# FinalSchematic1_2.net
KiCad netlist of a schematic drawn in EAGLE
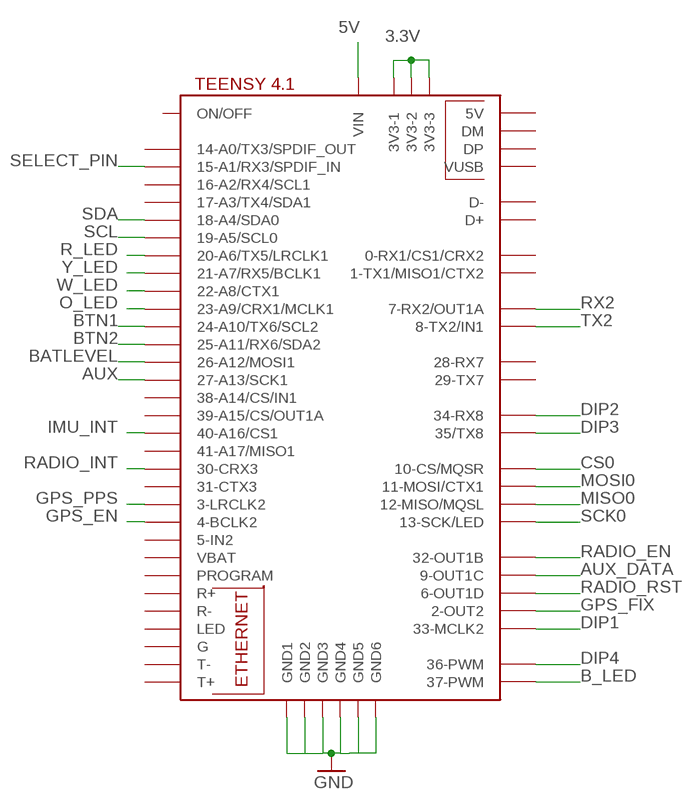
[diagram p0: schematic, sheet 1]
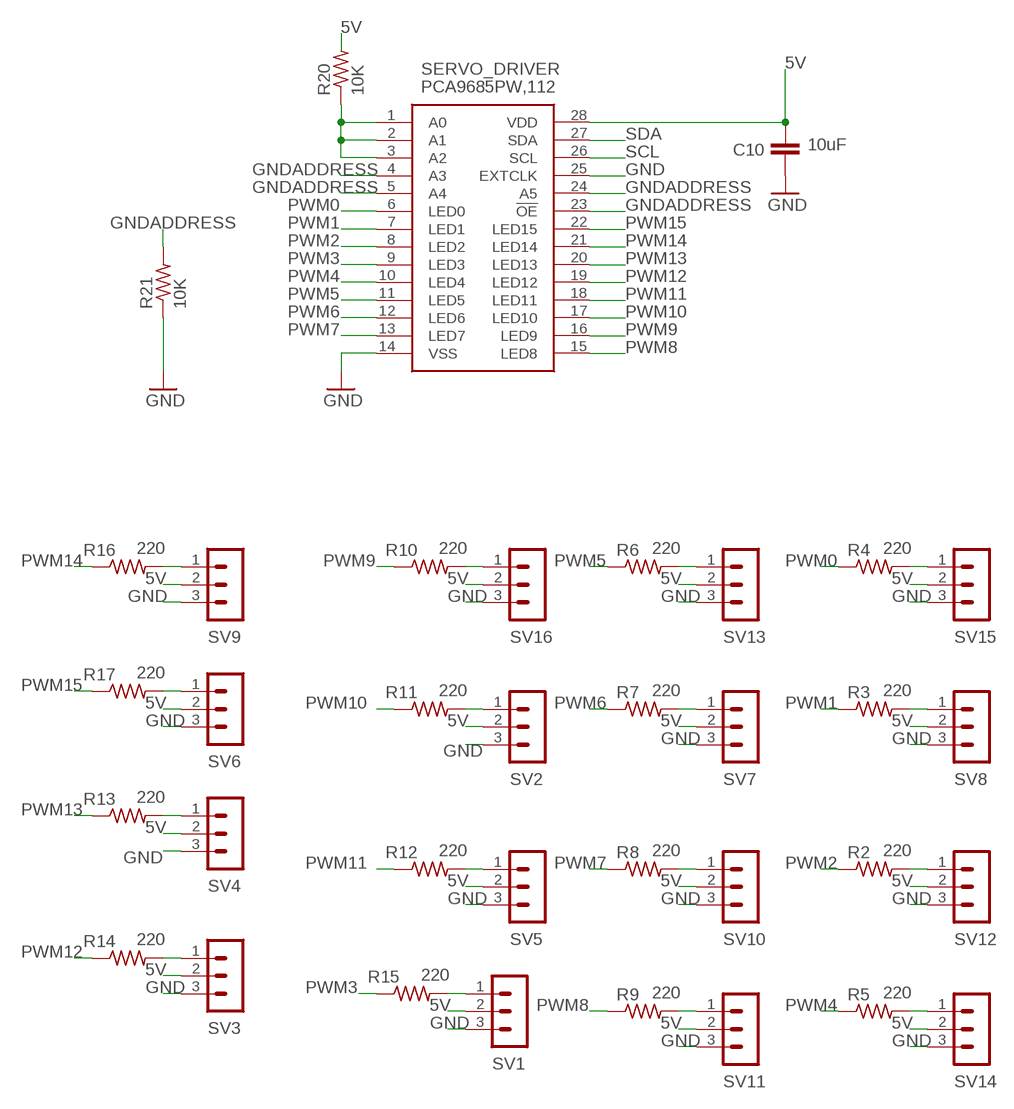
[diagram p1: schematic, sheet 2]
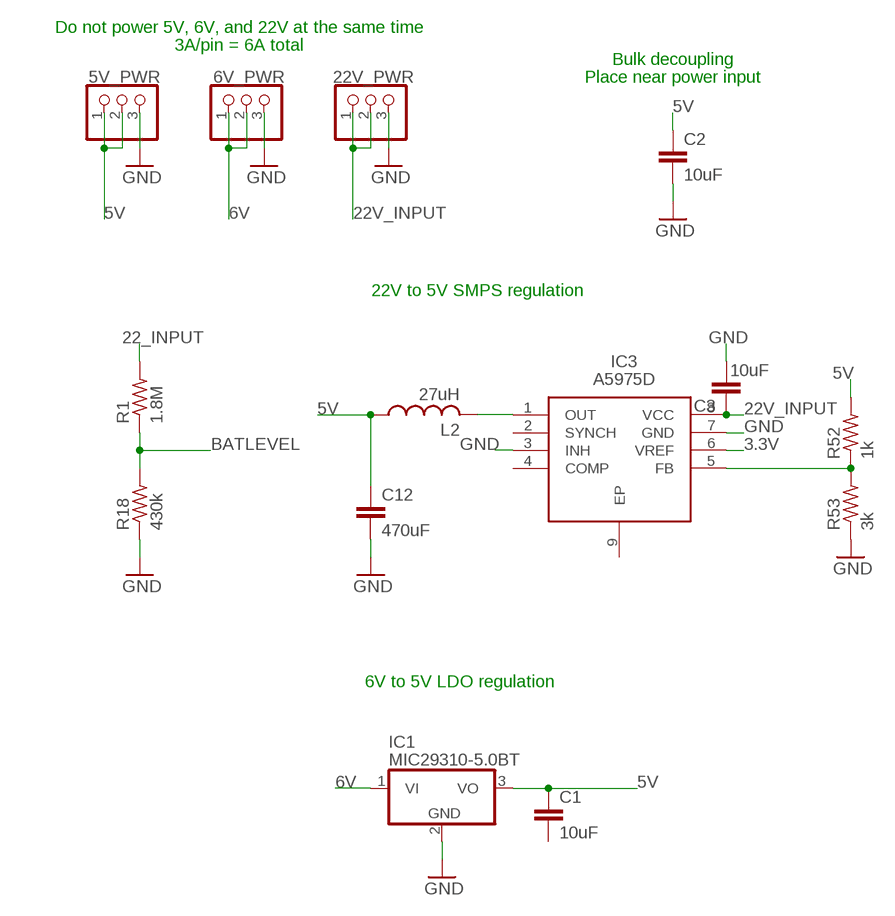
[diagram p2: schematic, sheet 3]
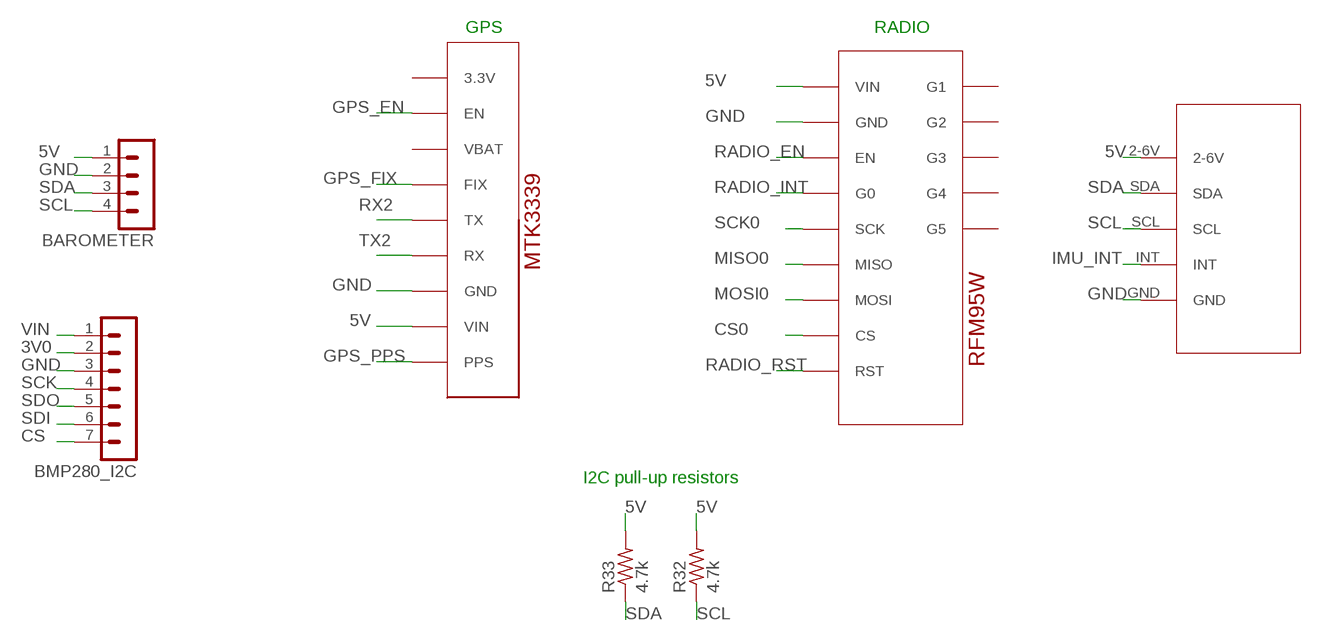
[diagram p3: schematic, sheet 4]
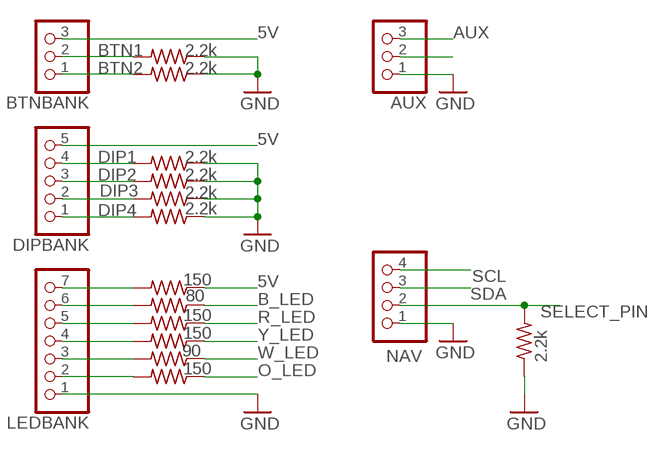
[diagram p4: schematic, sheet 5]
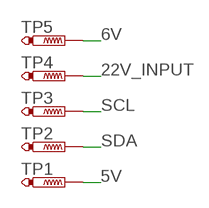
[diagram p5: schematic, sheet 6]

(export (version "E")
  (design (tool "Eeschema 10.0.6"))
  (components
    (comp (ref "C10")
      (value "10uF")
      (footprint "eagle-import:C2.5-3")
      (libsource (lib "eagle-import") (part "C2,5-3"))
    )
    (comp (ref "R2")
      (value "220")
      (footprint "eagle-import:0204_7")
      (libsource (lib "eagle-import") (part "R-US_0204/7"))
    )
    (comp (ref "R3")
      (value "220")
      (footprint "eagle-import:0204_7")
      (libsource (lib "eagle-import") (part "R-US_0204/7"))
    )
    (comp (ref "R4")
      (value "220")
      (footprint "eagle-import:0204_7")
      (libsource (lib "eagle-import") (part "R-US_0204/7"))
    )
    (comp (ref "R5")
      (value "220")
      (footprint "eagle-import:0204_7")
      (libsource (lib "eagle-import") (part "R-US_0204/7"))
    )
    (comp (ref "R6")
      (value "220")
      (footprint "eagle-import:0204_7")
      (libsource (lib "eagle-import") (part "R-US_0204/7"))
    )
    (comp (ref "R7")
      (value "220")
      (footprint "eagle-import:0204_7")
      (libsource (lib "eagle-import") (part "R-US_0204/7"))
    )
    (comp (ref "R8")
      (value "220")
      (footprint "eagle-import:0204_7")
      (libsource (lib "eagle-import") (part "R-US_0204/7"))
    )
    (comp (ref "R9")
      (value "220")
      (footprint "eagle-import:0204_7")
      (libsource (lib "eagle-import") (part "R-US_0204/7"))
    )
    (comp (ref "R10")
      (value "220")
      (footprint "eagle-import:0204_7")
      (libsource (lib "eagle-import") (part "R-US_0204/7"))
    )
    (comp (ref "R11")
      (value "220")
      (footprint "eagle-import:0204_7")
      (libsource (lib "eagle-import") (part "R-US_0204/7"))
    )
    (comp (ref "R12")
      (value "220")
      (footprint "eagle-import:0204_7")
      (libsource (lib "eagle-import") (part "R-US_0204/7"))
    )
    (comp (ref "R13")
      (value "220")
      (footprint "eagle-import:0204_7")
      (libsource (lib "eagle-import") (part "R-US_0204/7"))
    )
    (comp (ref "R14")
      (value "220")
      (footprint "eagle-import:0204_7")
      (libsource (lib "eagle-import") (part "R-US_0204/7"))
    )
    (comp (ref "R15")
      (value "220")
      (footprint "eagle-import:0204_7")
      (libsource (lib "eagle-import") (part "R-US_0204/7"))
    )
    (comp (ref "R16")
      (value "220")
      (footprint "eagle-import:0204_7")
      (libsource (lib "eagle-import") (part "R-US_0204/7"))
    )
    (comp (ref "R17")
      (value "220")
      (footprint "eagle-import:0204_7")
      (libsource (lib "eagle-import") (part "R-US_0204/7"))
    )
    (comp (ref "R20")
      (value "10K")
      (footprint "eagle-import:0204_7")
      (libsource (lib "eagle-import") (part "R-US_0204/7"))
    )
    (comp (ref "R21")
      (value "10K")
      (footprint "eagle-import:0204_7")
      (libsource (lib "eagle-import") (part "R-US_0204/7"))
    )
    (comp (ref "SERVO_DRIVER")
      (value "PCA9685PW,112")
      (footprint "eagle-import:SOP65P640X110-28N")
      (fields (field (name "MOUSER_PART_NUMBER") "771-PCA9685PW,112"))
      (libsource (lib "eagle-import") (part "PCA9685PW,112"))
    )
    (comp (ref "SV1")
      (value "MA03-1")
      (footprint "eagle-import:MA03-1")
      (libsource (lib "eagle-import") (part "MA03-1"))
    )
    (comp (ref "SV2")
      (value "MA03-1")
      (footprint "eagle-import:MA03-1")
      (libsource (lib "eagle-import") (part "MA03-1"))
    )
    (comp (ref "SV3")
      (value "MA03-1")
      (footprint "eagle-import:MA03-1")
      (libsource (lib "eagle-import") (part "MA03-1"))
    )
    (comp (ref "SV4")
      (value "MA03-1")
      (footprint "eagle-import:MA03-1")
      (libsource (lib "eagle-import") (part "MA03-1"))
    )
    (comp (ref "SV5")
      (value "MA03-1")
      (footprint "eagle-import:MA03-1")
      (libsource (lib "eagle-import") (part "MA03-1"))
    )
    (comp (ref "SV6")
      (value "MA03-1")
      (footprint "eagle-import:MA03-1")
      (libsource (lib "eagle-import") (part "MA03-1"))
    )
    (comp (ref "SV7")
      (value "MA03-1")
      (footprint "eagle-import:MA03-1")
      (libsource (lib "eagle-import") (part "MA03-1"))
    )
    (comp (ref "SV8")
      (value "MA03-1")
      (footprint "eagle-import:MA03-1")
      (libsource (lib "eagle-import") (part "MA03-1"))
    )
    (comp (ref "SV9")
      (value "MA03-1")
      (footprint "eagle-import:MA03-1")
      (libsource (lib "eagle-import") (part "MA03-1"))
    )
    (comp (ref "SV10")
      (value "MA03-1")
      (footprint "eagle-import:MA03-1")
      (libsource (lib "eagle-import") (part "MA03-1"))
    )
    (comp (ref "SV11")
      (value "MA03-1")
      (footprint "eagle-import:MA03-1")
      (libsource (lib "eagle-import") (part "MA03-1"))
    )
    (comp (ref "SV12")
      (value "MA03-1")
      (footprint "eagle-import:MA03-1")
      (libsource (lib "eagle-import") (part "MA03-1"))
    )
    (comp (ref "SV13")
      (value "MA03-1")
      (footprint "eagle-import:MA03-1")
      (libsource (lib "eagle-import") (part "MA03-1"))
    )
    (comp (ref "SV14")
      (value "MA03-1")
      (footprint "eagle-import:MA03-1")
      (libsource (lib "eagle-import") (part "MA03-1"))
    )
    (comp (ref "SV15")
      (value "MA03-1")
      (footprint "eagle-import:MA03-1")
      (libsource (lib "eagle-import") (part "MA03-1"))
    )
    (comp (ref "SV16")
      (value "MA03-1")
      (footprint "eagle-import:MA03-1")
      (libsource (lib "eagle-import") (part "MA03-1"))
    )
    (comp (ref "TEENSY4.1")
      (value "TEENSY41")
      (footprint "eagle-import:TEENSY41")
      (libsource (lib "eagle-import") (part "TEENSY41"))
    )
    (comp (ref "BAROMETER")
      (value "MA04-1")
      (footprint "eagle-import:MA04-1")
      (libsource (lib "eagle-import") (part "MA04-1"))
    )
    (comp (ref "BMP280_I2C")
      (value "MA07-1")
      (footprint "eagle-import:MA07-1")
      (libsource (lib "eagle-import") (part "MA07-1"))
    )
    (comp (ref "GPSMTK3339")
      (value "ADAFRUIT_MTK3339_GPS")
      (footprint "eagle-import:ADAFRUIT_MTK3339_GPS")
      (libsource (lib "eagle-import") (part "ADAFRUIT_MTK3339_GPS"))
    )
    (comp (ref "IMU")
      (value "ICM20948BREAKOUTDEVICE")
      (footprint "eagle-import:ICM20948BREAKOUT")
      (fields (field (name "SPICEPREFIX") "X"))
      (libsource (lib "eagle-import") (part "ICM20948BREAKOUTDEVICE"))
    )
    (comp (ref "R32")
      (value "4.7k")
      (footprint "eagle-import:0204_7")
      (libsource (lib "eagle-import") (part "R-US_0204/7"))
    )
    (comp (ref "R33")
      (value "4.7k")
      (footprint "eagle-import:0204_7")
      (libsource (lib "eagle-import") (part "R-US_0204/7"))
    )
    (comp (ref "RADIO")
      (value "ADAFRUIT_RFM95W_LORA_RADIO")
      (footprint "eagle-import:ADAFRUIT_RFM95W_LORA_RADIO")
      (libsource (lib "eagle-import") (part "ADAFRUIT_RFM95W_LORA_RADIO"))
    )
    (comp (ref "TP1")
      (value "PTR1B1,27")
      (footprint "eagle-import:B1,27")
      (libsource (lib "eagle-import") (part "PTR1B1,27"))
    )
    (comp (ref "TP2")
      (value "PTR1B1,27")
      (footprint "eagle-import:B1,27")
      (libsource (lib "eagle-import") (part "PTR1B1,27"))
    )
    (comp (ref "TP3")
      (value "PTR1B1,27")
      (footprint "eagle-import:B1,27")
      (libsource (lib "eagle-import") (part "PTR1B1,27"))
    )
    (comp (ref "TP4")
      (value "PTR1B1,27")
      (footprint "eagle-import:B1,27")
      (libsource (lib "eagle-import") (part "PTR1B1,27"))
    )
    (comp (ref "TP5")
      (value "PTR1B1,27")
      (footprint "eagle-import:B1,27")
      (libsource (lib "eagle-import") (part "PTR1B1,27"))
    )
    (comp (ref "AUX")
      (value "PINHD-1X3")
      (footprint "eagle-import:1X03")
      (libsource (lib "eagle-import") (part "PINHD-1X3"))
    )
    (comp (ref "BLUE")
      (value "80")
      (footprint "eagle-import:0204_7")
      (libsource (lib "eagle-import") (part "R-US_0204/7"))
    )
    (comp (ref "BTNBANK")
      (value "PINHD-1X3")
      (footprint "eagle-import:1X03")
      (libsource (lib "eagle-import") (part "PINHD-1X3"))
    )
    (comp (ref "DIPBANK")
      (value "PINHD-1X5")
      (footprint "eagle-import:1X05")
      (libsource (lib "eagle-import") (part "PINHD-1X5"))
    )
    (comp (ref "GREEN")
      (value "150")
      (footprint "eagle-import:0204_7")
      (libsource (lib "eagle-import") (part "R-US_0204/7"))
    )
    (comp (ref "LEDBANK")
      (value "PINHD-1X7")
      (footprint "eagle-import:1X07")
      (libsource (lib "eagle-import") (part "PINHD-1X7"))
    )
    (comp (ref "NAV")
      (value "PINHD-1X4")
      (footprint "eagle-import:1X04")
      (libsource (lib "eagle-import") (part "PINHD-1X4"))
    )
    (comp (ref "ORANGE")
      (value "150")
      (footprint "eagle-import:0204_7")
      (libsource (lib "eagle-import") (part "R-US_0204/7"))
    )
    (comp (ref "R19")
      (value "2.2k")
      (footprint "eagle-import:0204_7")
      (libsource (lib "eagle-import") (part "R-US_0204/7"))
    )
    (comp (ref "R22")
      (value "2.2k")
      (footprint "eagle-import:0204_7")
      (libsource (lib "eagle-import") (part "R-US_0204/7"))
    )
    (comp (ref "R23")
      (value "2.2k")
      (footprint "eagle-import:0204_7")
      (libsource (lib "eagle-import") (part "R-US_0204/7"))
    )
    (comp (ref "R34")
      (value "2.2k")
      (footprint "eagle-import:0204_7")
      (libsource (lib "eagle-import") (part "R-US_0204/7"))
    )
    (comp (ref "R35")
      (value "2.2k")
      (footprint "eagle-import:0204_7")
      (libsource (lib "eagle-import") (part "R-US_0204/7"))
    )
    (comp (ref "R36")
      (value "2.2k")
      (footprint "eagle-import:0204_7")
      (libsource (lib "eagle-import") (part "R-US_0204/7"))
    )
    (comp (ref "R37")
      (value "2.2k")
      (footprint "eagle-import:0204_7")
      (libsource (lib "eagle-import") (part "R-US_0204/7"))
    )
    (comp (ref "RED")
      (value "150")
      (footprint "eagle-import:0204_7")
      (libsource (lib "eagle-import") (part "R-US_0204/7"))
    )
    (comp (ref "WHITE")
      (value "90")
      (footprint "eagle-import:0204_7")
      (libsource (lib "eagle-import") (part "R-US_0204/7"))
    )
    (comp (ref "YELLOW")
      (value "150")
      (footprint "eagle-import:0204_7")
      (libsource (lib "eagle-import") (part "R-US_0204/7"))
    )
    (comp (ref "5V_PWR")
      (value "PINHD-1X3")
      (footprint "eagle-import:1X03")
      (libsource (lib "eagle-import") (part "PINHD-1X3"))
    )
    (comp (ref "6V_PWR")
      (value "PINHD-1X3")
      (footprint "eagle-import:1X03")
      (libsource (lib "eagle-import") (part "PINHD-1X3"))
    )
    (comp (ref "22V_PWR")
      (value "PINHD-1X3")
      (footprint "eagle-import:1X03")
      (libsource (lib "eagle-import") (part "PINHD-1X3"))
    )
    (comp (ref "C1")
      (value "10uF")
      (footprint "eagle-import:C2.5-3")
      (libsource (lib "eagle-import") (part "C2,5-3"))
    )
    (comp (ref "C2")
      (value "10uF")
      (footprint "eagle-import:C2.5-3")
      (libsource (lib "eagle-import") (part "C2,5-3"))
    )
    (comp (ref "C3")
      (value "10uF")
      (footprint "eagle-import:C2.5-3")
      (libsource (lib "eagle-import") (part "C2,5-3"))
    )
    (comp (ref "C12")
      (value "470uF")
      (footprint "eagle-import:C2.5-3")
      (libsource (lib "eagle-import") (part "C2,5-3"))
    )
    (comp (ref "IC1")
      (value "MIC29310-5.0BT")
      (footprint "eagle-import:TO220V")
      (libsource (lib "eagle-import") (part "78TV6"))
    )
    (comp (ref "IC3")
      (value "A5975D")
      (footprint "eagle-import:SOIC127P600X170-9N")
      (fields (field (name "MOUSER_PART_NUMBER") "511-A5975D"))
      (libsource (lib "eagle-import") (part "A5975D"))
    )
    (comp (ref "L2")
      (value "27uH")
      (footprint "eagle-import:TFI0307")
      (libsource (lib "eagle-import") (part "L-USTFI0307"))
    )
    (comp (ref "R1")
      (value "1.8M")
      (footprint "eagle-import:0204_7")
      (libsource (lib "eagle-import") (part "R-US_0204/7"))
    )
    (comp (ref "R18")
      (value "430k")
      (footprint "eagle-import:0204_7")
      (libsource (lib "eagle-import") (part "R-US_0204/7"))
    )
    (comp (ref "R52")
      (value "1k")
      (footprint "eagle-import:0204_7")
      (libsource (lib "eagle-import") (part "R-US_0204/7"))
    )
    (comp (ref "R53")
      (value "3k")
      (footprint "eagle-import:0204_7")
      (libsource (lib "eagle-import") (part "R-US_0204/7"))
    )
  )
  (nets
    (net (code "1") (name "3.3V") (class "Default")
      (node (ref "IC3") (pin "6") (pinfunction "VREF_6") (pintype "bidirectional"))
      (node (ref "TEENSY4.1") (pin "3V3-1") (pinfunction "3V3-1_3V3-1") (pintype "bidirectional"))
      (node (ref "TEENSY4.1") (pin "3V3-2") (pinfunction "3V3-2_3V3-2") (pintype "bidirectional"))
      (node (ref "TEENSY4.1") (pin "3V3-3") (pinfunction "3V3-3_3V3-3") (pintype "bidirectional"))
    )
    (net (code "2") (name "3V0") (class "Default")
      (node (ref "BMP280_I2C") (pin "2") (pinfunction "2_2") (pintype "passive"))
    )
    (net (code "3") (name "5V") (class "Default")
      (node (ref "5V_PWR") (pin "1") (pinfunction "1_1") (pintype "passive"))
      (node (ref "5V_PWR") (pin "2") (pinfunction "2_2") (pintype "passive"))
      (node (ref "BAROMETER") (pin "1") (pinfunction "1_1") (pintype "passive"))
      (node (ref "BTNBANK") (pin "3") (pinfunction "3_3") (pintype "passive"))
      (node (ref "C1") (pin "1") (pinfunction "1_1") (pintype "passive"))
      (node (ref "C10") (pin "1") (pinfunction "1_1") (pintype "passive"))
      (node (ref "C12") (pin "1") (pinfunction "1_1") (pintype "passive"))
      (node (ref "C2") (pin "1") (pinfunction "1_1") (pintype "passive"))
      (node (ref "DIPBANK") (pin "5") (pinfunction "5_5") (pintype "passive"))
      (node (ref "GPSMTK3339") (pin "VIN") (pinfunction "VIN_VIN") (pintype "bidirectional"))
      (node (ref "GREEN") (pin "1") (pinfunction "1_1") (pintype "passive"))
      (node (ref "IC1") (pin "3") (pinfunction "VO_3") (pintype "passive"))
      (node (ref "IMU") (pin "2-6V") (pinfunction "2-6V_2-6V") (pintype "bidirectional"))
      (node (ref "L2") (pin "1") (pinfunction "1_1") (pintype "passive"))
      (node (ref "R20") (pin "2") (pinfunction "2_2") (pintype "passive"))
      (node (ref "R32") (pin "2") (pinfunction "2_2") (pintype "passive"))
      (node (ref "R33") (pin "2") (pinfunction "2_2") (pintype "passive"))
      (node (ref "R52") (pin "2") (pinfunction "2_2") (pintype "passive"))
      (node (ref "RADIO") (pin "1") (pinfunction "VIN_1") (pintype "bidirectional"))
      (node (ref "SERVO_DRIVER") (pin "28") (pinfunction "VDD_28") (pintype "bidirectional"))
      (node (ref "SV1") (pin "2") (pinfunction "2_2") (pintype "passive"))
      (node (ref "SV10") (pin "2") (pinfunction "2_2") (pintype "passive"))
      (node (ref "SV11") (pin "2") (pinfunction "2_2") (pintype "passive"))
      (node (ref "SV12") (pin "2") (pinfunction "2_2") (pintype "passive"))
      (node (ref "SV13") (pin "2") (pinfunction "2_2") (pintype "passive"))
      (node (ref "SV14") (pin "2") (pinfunction "2_2") (pintype "passive"))
      (node (ref "SV15") (pin "2") (pinfunction "2_2") (pintype "passive"))
      (node (ref "SV16") (pin "2") (pinfunction "2_2") (pintype "passive"))
      (node (ref "SV2") (pin "2") (pinfunction "2_2") (pintype "passive"))
      (node (ref "SV3") (pin "2") (pinfunction "2_2") (pintype "passive"))
      (node (ref "SV4") (pin "2") (pinfunction "2_2") (pintype "passive"))
      (node (ref "SV5") (pin "2") (pinfunction "2_2") (pintype "passive"))
      (node (ref "SV6") (pin "2") (pinfunction "2_2") (pintype "passive"))
      (node (ref "SV7") (pin "2") (pinfunction "2_2") (pintype "passive"))
      (node (ref "SV8") (pin "2") (pinfunction "2_2") (pintype "passive"))
      (node (ref "SV9") (pin "2") (pinfunction "2_2") (pintype "passive"))
      (node (ref "TEENSY4.1") (pin "VIN") (pinfunction "VIN_VIN") (pintype "bidirectional"))
      (node (ref "TP1") (pin "TP") (pinfunction "TP_TP") (pintype "input"))
    )
    (net (code "4") (name "6V") (class "Default")
      (node (ref "6V_PWR") (pin "1") (pinfunction "1_1") (pintype "passive"))
      (node (ref "6V_PWR") (pin "2") (pinfunction "2_2") (pintype "passive"))
      (node (ref "IC1") (pin "1") (pinfunction "VI_1") (pintype "input"))
      (node (ref "TP5") (pin "TP") (pinfunction "TP_TP") (pintype "input"))
    )
    (net (code "5") (name "22V_INPUT") (class "Default")
      (node (ref "22V_PWR") (pin "1") (pinfunction "1_1") (pintype "passive"))
      (node (ref "22V_PWR") (pin "2") (pinfunction "2_2") (pintype "passive"))
      (node (ref "C3") (pin "1") (pinfunction "1_1") (pintype "passive"))
      (node (ref "IC3") (pin "8") (pinfunction "VCC_8") (pintype "bidirectional"))
      (node (ref "TP4") (pin "TP") (pinfunction "TP_TP") (pintype "input"))
    )
    (net (code "6") (name "22_INPUT") (class "Default")
      (node (ref "R1") (pin "2") (pinfunction "2_2") (pintype "passive"))
    )
    (net (code "7") (name "AUX") (class "Default")
      (node (ref "AUX") (pin "3") (pinfunction "3_3") (pintype "passive"))
      (node (ref "TEENSY4.1") (pin "27-A13/SCK1") (pinfunction "27-A13/SCK1_27-A13/SCK1") (pintype "bidirectional"))
    )
    (net (code "8") (name "AUX_DATA") (class "Default")
      (node (ref "TEENSY4.1") (pin "9-OUT1C") (pinfunction "9-OUT1C_9-OUT1C") (pintype "bidirectional"))
    )
    (net (code "9") (name "BATLEVEL") (class "Default")
      (node (ref "R1") (pin "1") (pinfunction "1_1") (pintype "passive"))
      (node (ref "R18") (pin "2") (pinfunction "2_2") (pintype "passive"))
      (node (ref "TEENSY4.1") (pin "26-A12/MOSI1") (pinfunction "26-A12/MOSI1_26-A12/MOSI1") (pintype "bidirectional"))
    )
    (net (code "10") (name "BTN1") (class "Default")
      (node (ref "BTNBANK") (pin "2") (pinfunction "2_2") (pintype "passive"))
      (node (ref "R19") (pin "2") (pinfunction "2_2") (pintype "passive"))
      (node (ref "TEENSY4.1") (pin "24-A10/TX6/SCL2") (pinfunction "24-A10/TX6/SCL2_24-A10/TX6/SCL2") (pintype "bidirectional"))
    )
    (net (code "11") (name "BTN2") (class "Default")
      (node (ref "BTNBANK") (pin "1") (pinfunction "1_1") (pintype "passive"))
      (node (ref "R22") (pin "2") (pinfunction "2_2") (pintype "passive"))
      (node (ref "TEENSY4.1") (pin "25-A11/RX6/SDA2") (pinfunction "25-A11/RX6/SDA2_25-A11/RX6/SDA2") (pintype "bidirectional"))
    )
    (net (code "12") (name "B_LED") (class "Default")
      (node (ref "BLUE") (pin "1") (pinfunction "1_1") (pintype "passive"))
      (node (ref "TEENSY4.1") (pin "37-PWM") (pinfunction "37-PWM_37-PWM") (pintype "bidirectional"))
    )
    (net (code "13") (name "CS") (class "Default")
      (node (ref "BMP280_I2C") (pin "7") (pinfunction "7_7") (pintype "passive"))
    )
    (net (code "14") (name "CS0") (class "Default")
      (node (ref "RADIO") (pin "8") (pinfunction "CS_8") (pintype "bidirectional"))
      (node (ref "TEENSY4.1") (pin "10-CS\\MQSR") (pinfunction "10-CS/MQSR_10-CS\\MQSR") (pintype "bidirectional"))
    )
    (net (code "15") (name "DIP1") (class "Default")
      (node (ref "DIPBANK") (pin "4") (pinfunction "4_4") (pintype "passive"))
      (node (ref "R37") (pin "2") (pinfunction "2_2") (pintype "passive"))
      (node (ref "TEENSY4.1") (pin "33-MCLK2") (pinfunction "33-MCLK2_33-MCLK2") (pintype "bidirectional"))
    )
    (net (code "16") (name "DIP2") (class "Default")
      (node (ref "DIPBANK") (pin "3") (pinfunction "3_3") (pintype "passive"))
      (node (ref "R36") (pin "2") (pinfunction "2_2") (pintype "passive"))
      (node (ref "TEENSY4.1") (pin "34-RX8") (pinfunction "34-RX8_34-RX8") (pintype "bidirectional"))
    )
    (net (code "17") (name "DIP3") (class "Default")
      (node (ref "DIPBANK") (pin "2") (pinfunction "2_2") (pintype "passive"))
      (node (ref "R34") (pin "2") (pinfunction "2_2") (pintype "passive"))
      (node (ref "TEENSY4.1") (pin "35-TX8") (pinfunction "35/TX8_35-TX8") (pintype "bidirectional"))
    )
    (net (code "18") (name "DIP4") (class "Default")
      (node (ref "DIPBANK") (pin "1") (pinfunction "1_1") (pintype "passive"))
      (node (ref "R35") (pin "2") (pinfunction "2_2") (pintype "passive"))
      (node (ref "TEENSY4.1") (pin "36-PWM") (pinfunction "36-PWM_36-PWM") (pintype "bidirectional"))
    )
    (net (code "19") (name "GND") (class "Default")
      (node (ref "22V_PWR") (pin "3") (pinfunction "3_3") (pintype "passive"))
      (node (ref "5V_PWR") (pin "3") (pinfunction "3_3") (pintype "passive"))
      (node (ref "6V_PWR") (pin "3") (pinfunction "3_3") (pintype "passive"))
      (node (ref "AUX") (pin "1") (pinfunction "1_1") (pintype "passive"))
      (node (ref "BAROMETER") (pin "2") (pinfunction "2_2") (pintype "passive"))
      (node (ref "BMP280_I2C") (pin "3") (pinfunction "3_3") (pintype "passive"))
      (node (ref "C10") (pin "2") (pinfunction "2_2") (pintype "passive"))
      (node (ref "C12") (pin "2") (pinfunction "2_2") (pintype "passive"))
      (node (ref "C2") (pin "2") (pinfunction "2_2") (pintype "passive"))
      (node (ref "C3") (pin "2") (pinfunction "2_2") (pintype "passive"))
      (node (ref "GPSMTK3339") (pin "GND") (pinfunction "GND_GND") (pintype "bidirectional"))
      (node (ref "IC1") (pin "2") (pinfunction "GND_2") (pintype "passive"))
      (node (ref "IC3") (pin "3") (pinfunction "INH_3") (pintype "bidirectional"))
      (node (ref "IC3") (pin "7") (pinfunction "GND_7") (pintype "bidirectional"))
      (node (ref "IMU") (pin "GND") (pinfunction "GND_GND") (pintype "bidirectional"))
      (node (ref "LEDBANK") (pin "1") (pinfunction "1_1") (pintype "passive"))
      (node (ref "NAV") (pin "1") (pinfunction "1_1") (pintype "passive"))
      (node (ref "R18") (pin "1") (pinfunction "1_1") (pintype "passive"))
      (node (ref "R19") (pin "1") (pinfunction "1_1") (pintype "passive"))
      (node (ref "R21") (pin "1") (pinfunction "1_1") (pintype "passive"))
      (node (ref "R22") (pin "1") (pinfunction "1_1") (pintype "passive"))
      (node (ref "R23") (pin "1") (pinfunction "1_1") (pintype "passive"))
      (node (ref "R34") (pin "1") (pinfunction "1_1") (pintype "passive"))
      (node (ref "R35") (pin "1") (pinfunction "1_1") (pintype "passive"))
      (node (ref "R36") (pin "1") (pinfunction "1_1") (pintype "passive"))
      (node (ref "R37") (pin "1") (pinfunction "1_1") (pintype "passive"))
      (node (ref "R53") (pin "1") (pinfunction "1_1") (pintype "passive"))
      (node (ref "RADIO") (pin "2") (pinfunction "GND_2") (pintype "bidirectional"))
      (node (ref "SERVO_DRIVER") (pin "14") (pinfunction "VSS_14") (pintype "bidirectional"))
      (node (ref "SERVO_DRIVER") (pin "25") (pinfunction "EXTCLK_25") (pintype "bidirectional"))
      (node (ref "SV1") (pin "3") (pinfunction "3_3") (pintype "passive"))
      (node (ref "SV10") (pin "3") (pinfunction "3_3") (pintype "passive"))
      (node (ref "SV11") (pin "3") (pinfunction "3_3") (pintype "passive"))
      (node (ref "SV12") (pin "3") (pinfunction "3_3") (pintype "passive"))
      (node (ref "SV13") (pin "3") (pinfunction "3_3") (pintype "passive"))
      (node (ref "SV14") (pin "3") (pinfunction "3_3") (pintype "passive"))
      (node (ref "SV15") (pin "3") (pinfunction "3_3") (pintype "passive"))
      (node (ref "SV16") (pin "3") (pinfunction "3_3") (pintype "passive"))
      (node (ref "SV2") (pin "3") (pinfunction "3_3") (pintype "passive"))
      (node (ref "SV3") (pin "3") (pinfunction "3_3") (pintype "passive"))
      (node (ref "SV4") (pin "3") (pinfunction "3_3") (pintype "passive"))
      (node (ref "SV5") (pin "3") (pinfunction "3_3") (pintype "passive"))
      (node (ref "SV6") (pin "3") (pinfunction "3_3") (pintype "passive"))
      (node (ref "SV7") (pin "3") (pinfunction "3_3") (pintype "passive"))
      (node (ref "SV8") (pin "3") (pinfunction "3_3") (pintype "passive"))
      (node (ref "SV9") (pin "3") (pinfunction "3_3") (pintype "passive"))
      (node (ref "TEENSY4.1") (pin "GND1") (pinfunction "GND1_GND1") (pintype "bidirectional"))
      (node (ref "TEENSY4.1") (pin "GND2") (pinfunction "GND2_GND2") (pintype "bidirectional"))
      (node (ref "TEENSY4.1") (pin "GND3") (pinfunction "GND3_GND3") (pintype "bidirectional"))
      (node (ref "TEENSY4.1") (pin "GND4") (pinfunction "GND4_GND4") (pintype "bidirectional"))
      (node (ref "TEENSY4.1") (pin "GND5") (pinfunction "GND5_GND5") (pintype "bidirectional"))
      (node (ref "TEENSY4.1") (pin "GND6") (pinfunction "GND6_GND6") (pintype "bidirectional"))
    )
    (net (code "20") (name "GNDADDRESS") (class "Default")
      (node (ref "R21") (pin "2") (pinfunction "2_2") (pintype "passive"))
      (node (ref "SERVO_DRIVER") (pin "23") (pinfunction "~{OE}_23") (pintype "bidirectional"))
      (node (ref "SERVO_DRIVER") (pin "24") (pinfunction "A5_24") (pintype "bidirectional"))
      (node (ref "SERVO_DRIVER") (pin "4") (pinfunction "A3_4") (pintype "bidirectional"))
      (node (ref "SERVO_DRIVER") (pin "5") (pinfunction "A4_5") (pintype "bidirectional"))
    )
    (net (code "21") (name "GPS_EN") (class "Default")
      (node (ref "GPSMTK3339") (pin "EN") (pinfunction "EN_EN") (pintype "bidirectional"))
      (node (ref "TEENSY4.1") (pin "4-BCLK2") (pinfunction "4-BCLK2_4-BCLK2") (pintype "bidirectional"))
    )
    (net (code "22") (name "GPS_FIX") (class "Default")
      (node (ref "GPSMTK3339") (pin "FIX") (pinfunction "FIX_FIX") (pintype "bidirectional"))
      (node (ref "TEENSY4.1") (pin "2-OUT2") (pinfunction "2-OUT2_2-OUT2") (pintype "bidirectional"))
    )
    (net (code "23") (name "GPS_PPS") (class "Default")
      (node (ref "GPSMTK3339") (pin "PPS") (pinfunction "PPS_PPS") (pintype "bidirectional"))
      (node (ref "TEENSY4.1") (pin "3-LRCLK2") (pinfunction "3-LRCLK2_3-LRCLK2") (pintype "bidirectional"))
    )
    (net (code "24") (name "IMU_INT") (class "Default")
      (node (ref "IMU") (pin "INT") (pinfunction "INT_INT") (pintype "bidirectional"))
      (node (ref "TEENSY4.1") (pin "40-A16/CS1") (pinfunction "40-A16/CS1_40-A16/CS1") (pintype "bidirectional"))
    )
    (net (code "25") (name "MISO0") (class "Default")
      (node (ref "RADIO") (pin "6") (pinfunction "MISO_6") (pintype "bidirectional"))
      (node (ref "TEENSY4.1") (pin "12-MISO/MQSL") (pinfunction "12-MISO/MQSL_12-MISO/MQSL") (pintype "bidirectional"))
    )
    (net (code "26") (name "MOSI0") (class "Default")
      (node (ref "RADIO") (pin "7") (pinfunction "MOSI_7") (pintype "bidirectional"))
      (node (ref "TEENSY4.1") (pin "11-MOSI/CTX1") (pinfunction "11-MOSI/CTX1_11-MOSI/CTX1") (pintype "bidirectional"))
    )
    (net (code "27") (name "Net-(BLUE-Pad2)") (class "Default")
      (node (ref "BLUE") (pin "2") (pinfunction "2_2") (pintype "passive"))
      (node (ref "LEDBANK") (pin "6") (pinfunction "6_6") (pintype "passive"))
    )
    (net (code "28") (name "Net-(GREEN-Pad2)") (class "Default")
      (node (ref "GREEN") (pin "2") (pinfunction "2_2") (pintype "passive"))
      (node (ref "LEDBANK") (pin "7") (pinfunction "7_7") (pintype "passive"))
    )
    (net (code "29") (name "Net-(IC3-FB)") (class "Default")
      (node (ref "IC3") (pin "5") (pinfunction "FB_5") (pintype "bidirectional"))
      (node (ref "R52") (pin "1") (pinfunction "1_1") (pintype "passive"))
      (node (ref "R53") (pin "2") (pinfunction "2_2") (pintype "passive"))
    )
    (net (code "30") (name "Net-(IC3-OUT)") (class "Default")
      (node (ref "IC3") (pin "1") (pinfunction "OUT_1") (pintype "bidirectional"))
      (node (ref "L2") (pin "2") (pinfunction "2_2") (pintype "passive"))
    )
    (net (code "31") (name "Net-(LEDBANK-Pad2)") (class "Default")
      (node (ref "LEDBANK") (pin "2") (pinfunction "2_2") (pintype "passive"))
      (node (ref "ORANGE") (pin "2") (pinfunction "2_2") (pintype "passive"))
    )
    (net (code "32") (name "Net-(LEDBANK-Pad3)") (class "Default")
      (node (ref "LEDBANK") (pin "3") (pinfunction "3_3") (pintype "passive"))
      (node (ref "WHITE") (pin "2") (pinfunction "2_2") (pintype "passive"))
    )
    (net (code "33") (name "Net-(LEDBANK-Pad4)") (class "Default")
      (node (ref "LEDBANK") (pin "4") (pinfunction "4_4") (pintype "passive"))
      (node (ref "YELLOW") (pin "2") (pinfunction "2_2") (pintype "passive"))
    )
    (net (code "34") (name "Net-(LEDBANK-Pad5)") (class "Default")
      (node (ref "LEDBANK") (pin "5") (pinfunction "5_5") (pintype "passive"))
      (node (ref "RED") (pin "2") (pinfunction "2_2") (pintype "passive"))
    )
    (net (code "35") (name "Net-(R2-Pad2)") (class "Default")
      (node (ref "R2") (pin "2") (pinfunction "2_2") (pintype "passive"))
      (node (ref "SV12") (pin "1") (pinfunction "1_1") (pintype "passive"))
    )
    (net (code "36") (name "Net-(R3-Pad2)") (class "Default")
      (node (ref "R3") (pin "2") (pinfunction "2_2") (pintype "passive"))
      (node (ref "SV8") (pin "1") (pinfunction "1_1") (pintype "passive"))
    )
    (net (code "37") (name "Net-(R4-Pad2)") (class "Default")
      (node (ref "R4") (pin "2") (pinfunction "2_2") (pintype "passive"))
      (node (ref "SV15") (pin "1") (pinfunction "1_1") (pintype "passive"))
    )
    (net (code "38") (name "Net-(R5-Pad2)") (class "Default")
      (node (ref "R5") (pin "2") (pinfunction "2_2") (pintype "passive"))
      (node (ref "SV14") (pin "1") (pinfunction "1_1") (pintype "passive"))
    )
    (net (code "39") (name "Net-(R6-Pad2)") (class "Default")
      (node (ref "R6") (pin "2") (pinfunction "2_2") (pintype "passive"))
      (node (ref "SV13") (pin "1") (pinfunction "1_1") (pintype "passive"))
    )
    (net (code "40") (name "Net-(R7-Pad2)") (class "Default")
      (node (ref "R7") (pin "2") (pinfunction "2_2") (pintype "passive"))
      (node (ref "SV7") (pin "1") (pinfunction "1_1") (pintype "passive"))
    )
    (net (code "41") (name "Net-(R8-Pad2)") (class "Default")
      (node (ref "R8") (pin "2") (pinfunction "2_2") (pintype "passive"))
      (node (ref "SV10") (pin "1") (pinfunction "1_1") (pintype "passive"))
    )
    (net (code "42") (name "Net-(R9-Pad2)") (class "Default")
      (node (ref "R9") (pin "2") (pinfunction "2_2") (pintype "passive"))
      (node (ref "SV11") (pin "1") (pinfunction "1_1") (pintype "passive"))
    )
    (net (code "43") (name "Net-(R10-Pad2)") (class "Default")
      (node (ref "R10") (pin "2") (pinfunction "2_2") (pintype "passive"))
      (node (ref "SV16") (pin "1") (pinfunction "1_1") (pintype "passive"))
    )
    (net (code "44") (name "Net-(R11-Pad2)") (class "Default")
      (node (ref "R11") (pin "2") (pinfunction "2_2") (pintype "passive"))
      (node (ref "SV2") (pin "1") (pinfunction "1_1") (pintype "passive"))
    )
    (net (code "45") (name "Net-(R12-Pad2)") (class "Default")
      (node (ref "R12") (pin "2") (pinfunction "2_2") (pintype "passive"))
      (node (ref "SV5") (pin "1") (pinfunction "1_1") (pintype "passive"))
    )
    (net (code "46") (name "Net-(R13-Pad2)") (class "Default")
      (node (ref "R13") (pin "2") (pinfunction "2_2") (pintype "passive"))
      (node (ref "SV4") (pin "1") (pinfunction "1_1") (pintype "passive"))
    )
    (net (code "47") (name "Net-(R14-Pad2)") (class "Default")
      (node (ref "R14") (pin "2") (pinfunction "2_2") (pintype "passive"))
      (node (ref "SV3") (pin "1") (pinfunction "1_1") (pintype "passive"))
    )
    (net (code "48") (name "Net-(R15-Pad2)") (class "Default")
      (node (ref "R15") (pin "2") (pinfunction "2_2") (pintype "passive"))
      (node (ref "SV1") (pin "1") (pinfunction "1_1") (pintype "passive"))
    )
    (net (code "49") (name "Net-(R16-Pad2)") (class "Default")
      (node (ref "R16") (pin "2") (pinfunction "2_2") (pintype "passive"))
      (node (ref "SV9") (pin "1") (pinfunction "1_1") (pintype "passive"))
    )
    (net (code "50") (name "Net-(R17-Pad2)") (class "Default")
      (node (ref "R17") (pin "2") (pinfunction "2_2") (pintype "passive"))
      (node (ref "SV6") (pin "1") (pinfunction "1_1") (pintype "passive"))
    )
    (net (code "51") (name "Net-(SERVO_DRIVER-A0)") (class "Default")
      (node (ref "R20") (pin "1") (pinfunction "1_1") (pintype "passive"))
      (node (ref "SERVO_DRIVER") (pin "1") (pinfunction "A0_1") (pintype "bidirectional"))
      (node (ref "SERVO_DRIVER") (pin "2") (pinfunction "A1_2") (pintype "bidirectional"))
      (node (ref "SERVO_DRIVER") (pin "3") (pinfunction "A2_3") (pintype "bidirectional"))
    )
    (net (code "52") (name "O_LED") (class "Default")
      (node (ref "ORANGE") (pin "1") (pinfunction "1_1") (pintype "passive"))
      (node (ref "TEENSY4.1") (pin "23-A9/CRX1/MCLK1") (pinfunction "23-A9/CRX1/MCLK1_23-A9/CRX1/MCLK1") (pintype "bidirectional"))
    )
    (net (code "53") (name "PWM0") (class "Default")
      (node (ref "R4") (pin "1") (pinfunction "1_1") (pintype "passive"))
      (node (ref "SERVO_DRIVER") (pin "6") (pinfunction "LED0_6") (pintype "bidirectional"))
    )
    (net (code "54") (name "PWM1") (class "Default")
      (node (ref "R3") (pin "1") (pinfunction "1_1") (pintype "passive"))
      (node (ref "SERVO_DRIVER") (pin "7") (pinfunction "LED1_7") (pintype "bidirectional"))
    )
    (net (code "55") (name "PWM2") (class "Default")
      (node (ref "R2") (pin "1") (pinfunction "1_1") (pintype "passive"))
      (node (ref "SERVO_DRIVER") (pin "8") (pinfunction "LED2_8") (pintype "bidirectional"))
    )
    (net (code "56") (name "PWM3") (class "Default")
      (node (ref "R15") (pin "1") (pinfunction "1_1") (pintype "passive"))
      (node (ref "SERVO_DRIVER") (pin "9") (pinfunction "LED3_9") (pintype "bidirectional"))
    )
    (net (code "57") (name "PWM4") (class "Default")
      (node (ref "R5") (pin "1") (pinfunction "1_1") (pintype "passive"))
      (node (ref "SERVO_DRIVER") (pin "10") (pinfunction "LED4_10") (pintype "bidirectional"))
    )
    (net (code "58") (name "PWM5") (class "Default")
      (node (ref "R6") (pin "1") (pinfunction "1_1") (pintype "passive"))
      (node (ref "SERVO_DRIVER") (pin "11") (pinfunction "LED5_11") (pintype "bidirectional"))
    )
    (net (code "59") (name "PWM6") (class "Default")
      (node (ref "R7") (pin "1") (pinfunction "1_1") (pintype "passive"))
      (node (ref "SERVO_DRIVER") (pin "12") (pinfunction "LED6_12") (pintype "bidirectional"))
    )
    (net (code "60") (name "PWM7") (class "Default")
      (node (ref "R8") (pin "1") (pinfunction "1_1") (pintype "passive"))
      (node (ref "SERVO_DRIVER") (pin "13") (pinfunction "LED7_13") (pintype "bidirectional"))
    )
    (net (code "61") (name "PWM8") (class "Default")
      (node (ref "R9") (pin "1") (pinfunction "1_1") (pintype "passive"))
      (node (ref "SERVO_DRIVER") (pin "15") (pinfunction "LED8_15") (pintype "bidirectional"))
    )
    (net (code "62") (name "PWM9") (class "Default")
      (node (ref "R10") (pin "1") (pinfunction "1_1") (pintype "passive"))
      (node (ref "SERVO_DRIVER") (pin "16") (pinfunction "LED9_16") (pintype "bidirectional"))
    )
    (net (code "63") (name "PWM10") (class "Default")
      (node (ref "R11") (pin "1") (pinfunction "1_1") (pintype "passive"))
      (node (ref "SERVO_DRIVER") (pin "17") (pinfunction "LED10_17") (pintype "bidirectional"))
    )
    (net (code "64") (name "PWM11") (class "Default")
      (node (ref "R12") (pin "1") (pinfunction "1_1") (pintype "passive"))
      (node (ref "SERVO_DRIVER") (pin "18") (pinfunction "LED11_18") (pintype "bidirectional"))
    )
    (net (code "65") (name "PWM12") (class "Default")
      (node (ref "R14") (pin "1") (pinfunction "1_1") (pintype "passive"))
      (node (ref "SERVO_DRIVER") (pin "19") (pinfunction "LED12_19") (pintype "bidirectional"))
    )
    (net (code "66") (name "PWM13") (class "Default")
      (node (ref "R13") (pin "1") (pinfunction "1_1") (pintype "passive"))
      (node (ref "SERVO_DRIVER") (pin "20") (pinfunction "LED13_20") (pintype "bidirectional"))
    )
    (net (code "67") (name "PWM14") (class "Default")
      (node (ref "R16") (pin "1") (pinfunction "1_1") (pintype "passive"))
      (node (ref "SERVO_DRIVER") (pin "21") (pinfunction "LED14_21") (pintype "bidirectional"))
    )
    (net (code "68") (name "PWM15") (class "Default")
      (node (ref "R17") (pin "1") (pinfunction "1_1") (pintype "passive"))
      (node (ref "SERVO_DRIVER") (pin "22") (pinfunction "LED15_22") (pintype "bidirectional"))
    )
    (net (code "69") (name "RADIO_EN") (class "Default")
      (node (ref "RADIO") (pin "3") (pinfunction "EN_3") (pintype "bidirectional"))
      (node (ref "TEENSY4.1") (pin "32-OUT1B") (pinfunction "32-OUT1B_32-OUT1B") (pintype "bidirectional"))
    )
    (net (code "70") (name "RADIO_INT") (class "Default")
      (node (ref "RADIO") (pin "4") (pinfunction "G0_4") (pintype "bidirectional"))
      (node (ref "TEENSY4.1") (pin "30-CRX3") (pinfunction "30-CRX3_30-CRX3") (pintype "bidirectional"))
    )
    (net (code "71") (name "RADIO_RST") (class "Default")
      (node (ref "RADIO") (pin "9") (pinfunction "RST_9") (pintype "bidirectional"))
      (node (ref "TEENSY4.1") (pin "6-OUT1D") (pinfunction "6-OUT1D_6-OUT1D") (pintype "bidirectional"))
    )
    (net (code "72") (name "RX2") (class "Default")
      (node (ref "GPSMTK3339") (pin "TX") (pinfunction "TX_TX") (pintype "bidirectional"))
      (node (ref "TEENSY4.1") (pin "7-RX2/OUT1A") (pinfunction "7-RX2/OUT1A_7-RX2/OUT1A") (pintype "bidirectional"))
    )
    (net (code "73") (name "R_LED") (class "Default")
      (node (ref "RED") (pin "1") (pinfunction "1_1") (pintype "passive"))
      (node (ref "TEENSY4.1") (pin "20-A6/TX5/LRCLK1") (pinfunction "20-A6/TX5/LRCLK1_20-A6/TX5/LRCLK1") (pintype "bidirectional"))
    )
    (net (code "74") (name "SCK") (class "Default")
      (node (ref "BMP280_I2C") (pin "4") (pinfunction "4_4") (pintype "passive"))
    )
    (net (code "75") (name "SCK0") (class "Default")
      (node (ref "RADIO") (pin "5") (pinfunction "SCK_5") (pintype "bidirectional"))
      (node (ref "TEENSY4.1") (pin "13-SCK/LED") (pinfunction "13-SCK/LED_13-SCK/LED") (pintype "bidirectional"))
    )
    (net (code "76") (name "SCL") (class "Default")
      (node (ref "BAROMETER") (pin "4") (pinfunction "4_4") (pintype "passive"))
      (node (ref "IMU") (pin "SCL") (pinfunction "SCL_SCL") (pintype "bidirectional"))
      (node (ref "NAV") (pin "4") (pinfunction "4_4") (pintype "passive"))
      (node (ref "R32") (pin "1") (pinfunction "1_1") (pintype "passive"))
      (node (ref "SERVO_DRIVER") (pin "26") (pinfunction "SCL_26") (pintype "bidirectional"))
      (node (ref "TEENSY4.1") (pin "19-A5/SCL0") (pinfunction "19-A5/SCL0_19-A5/SCL0") (pintype "bidirectional"))
      (node (ref "TP3") (pin "TP") (pinfunction "TP_TP") (pintype "input"))
    )
    (net (code "77") (name "SDA") (class "Default")
      (node (ref "BAROMETER") (pin "3") (pinfunction "3_3") (pintype "passive"))
      (node (ref "IMU") (pin "SDA") (pinfunction "SDA_SDA") (pintype "bidirectional"))
      (node (ref "NAV") (pin "3") (pinfunction "3_3") (pintype "passive"))
      (node (ref "R33") (pin "1") (pinfunction "1_1") (pintype "passive"))
      (node (ref "SERVO_DRIVER") (pin "27") (pinfunction "SDA_27") (pintype "bidirectional"))
      (node (ref "TEENSY4.1") (pin "18-A4/SDA0") (pinfunction "18-A4/SDA0_18-A4/SDA0") (pintype "bidirectional"))
      (node (ref "TP2") (pin "TP") (pinfunction "TP_TP") (pintype "input"))
    )
    (net (code "78") (name "SDI") (class "Default")
      (node (ref "BMP280_I2C") (pin "6") (pinfunction "6_6") (pintype "passive"))
    )
    (net (code "79") (name "SDO") (class "Default")
      (node (ref "BMP280_I2C") (pin "5") (pinfunction "5_5") (pintype "passive"))
    )
    (net (code "80") (name "SELECT_PIN") (class "Default")
      (node (ref "NAV") (pin "2") (pinfunction "2_2") (pintype "passive"))
      (node (ref "R23") (pin "2") (pinfunction "2_2") (pintype "passive"))
      (node (ref "TEENSY4.1") (pin "15-A1/RX3/SPDIF_IN") (pinfunction "15-A1/RX3/SPDIF_IN_15-A1/RX3/SPDIF_IN") (pintype "bidirectional"))
    )
    (net (code "81") (name "TX2") (class "Default")
      (node (ref "GPSMTK3339") (pin "RX") (pinfunction "RX_RX") (pintype "bidirectional"))
      (node (ref "TEENSY4.1") (pin "8-TX2/IN1") (pinfunction "8-TX2/IN1_8-TX2/IN1") (pintype "bidirectional"))
    )
    (net (code "82") (name "VIN") (class "Default")
      (node (ref "BMP280_I2C") (pin "1") (pinfunction "1_1") (pintype "passive"))
    )
    (net (code "83") (name "W_LED") (class "Default")
      (node (ref "TEENSY4.1") (pin "22-A8/CTX1") (pinfunction "22-A8/CTX1_22-A8/CTX1") (pintype "bidirectional"))
      (node (ref "WHITE") (pin "1") (pinfunction "1_1") (pintype "passive"))
    )
    (net (code "84") (name "Y_LED") (class "Default")
      (node (ref "TEENSY4.1") (pin "21-A7/RX5/BCLK1") (pinfunction "21-A7/RX5/BCLK1_21-A7/RX5/BCLK1") (pintype "bidirectional"))
      (node (ref "YELLOW") (pin "1") (pinfunction "1_1") (pintype "passive"))
    )
    (net (code "85") (name "unconnected-(AUX-Pad2)") (class "Default")
      (node (ref "AUX") (pin "2") (pinfunction "2_2") (pintype "passive"))
    )
    (net (code "86") (name "unconnected-(C1-Pad2)") (class "Default")
      (node (ref "C1") (pin "2") (pinfunction "2_2") (pintype "passive"))
    )
    (net (code "87") (name "unconnected-(GPSMTK3339-Pad3.3V)") (class "Default")
      (node (ref "GPSMTK3339") (pin "3.3V") (pinfunction "3.3V_3.3V") (pintype "bidirectional"))
    )
    (net (code "88") (name "unconnected-(GPSMTK3339-PadVBAT)") (class "Default")
      (node (ref "GPSMTK3339") (pin "VBAT") (pinfunction "VBAT_VBAT") (pintype "bidirectional"))
    )
    (net (code "89") (name "unconnected-(IC3-COMP-Pad4)") (class "Default")
      (node (ref "IC3") (pin "4") (pinfunction "COMP_4") (pintype "bidirectional"))
    )
    (net (code "90") (name "unconnected-(IC3-EP-Pad9)") (class "Default")
      (node (ref "IC3") (pin "9") (pinfunction "EP_9") (pintype "bidirectional"))
    )
    (net (code "91") (name "unconnected-(IC3-SYNCH-Pad2)") (class "Default")
      (node (ref "IC3") (pin "2") (pinfunction "SYNCH_2") (pintype "bidirectional"))
    )
    (net (code "92") (name "unconnected-(RADIO-G1-Pad10)") (class "Default")
      (node (ref "RADIO") (pin "10") (pinfunction "G1_10") (pintype "bidirectional"))
    )
    (net (code "93") (name "unconnected-(RADIO-G2-Pad11)") (class "Default")
      (node (ref "RADIO") (pin "11") (pinfunction "G2_11") (pintype "bidirectional"))
    )
    (net (code "94") (name "unconnected-(RADIO-G3-Pad12)") (class "Default")
      (node (ref "RADIO") (pin "12") (pinfunction "G3_12") (pintype "bidirectional"))
    )
    (net (code "95") (name "unconnected-(RADIO-G4-Pad13)") (class "Default")
      (node (ref "RADIO") (pin "13") (pinfunction "G4_13") (pintype "bidirectional"))
    )
    (net (code "96") (name "unconnected-(RADIO-G5-Pad14)") (class "Default")
      (node (ref "RADIO") (pin "14") (pinfunction "G5_14") (pintype "bidirectional"))
    )
    (net (code "97") (name "unconnected-(TEENSY4.1-5V-Pad+5V)") (class "Default")
      (node (ref "TEENSY4.1") (pin "+5V") (pinfunction "5V_+5V") (pintype "bidirectional"))
    )
    (net (code "98") (name "unconnected-(TEENSY4.1-Pad0-RX1{slash}CS1{slash}CRX2)") (class "Default")
      (node (ref "TEENSY4.1") (pin "0-RX1/CS1/CRX2") (pinfunction "0-RX1/CS1/CRX2_0-RX1/CS1/CRX2") (pintype "bidirectional"))
    )
    (net (code "99") (name "unconnected-(TEENSY4.1-Pad1-TX1{slash}MISO1{slash}CTX2)") (class "Default")
      (node (ref "TEENSY4.1") (pin "1-TX1/MISO1/CTX2") (pinfunction "1-TX1/MISO1/CTX2_1-TX1/MISO1/CTX2") (pintype "bidirectional"))
    )
    (net (code "100") (name "unconnected-(TEENSY4.1-Pad5-IN2)") (class "Default")
      (node (ref "TEENSY4.1") (pin "5-IN2") (pinfunction "5-IN2_5-IN2") (pintype "bidirectional"))
    )
    (net (code "101") (name "unconnected-(TEENSY4.1-Pad14-A0{slash}TX3{slash}SPDIF_OUT)") (class "Default")
      (node (ref "TEENSY4.1") (pin "14-A0/TX3/SPDIF_OUT") (pinfunction "14-A0/TX3/SPDIF_OUT_14-A0/TX3/SPDIF_OUT") (pintype "bidirectional"))
    )
    (net (code "102") (name "unconnected-(TEENSY4.1-Pad16-A2{slash}RX4{slash}SCL1)") (class "Default")
      (node (ref "TEENSY4.1") (pin "16-A2/RX4/SCL1") (pinfunction "16-A2/RX4/SCL1_16-A2/RX4/SCL1") (pintype "bidirectional"))
    )
    (net (code "103") (name "unconnected-(TEENSY4.1-Pad17-A3{slash}TX4{slash}SDA1)") (class "Default")
      (node (ref "TEENSY4.1") (pin "17-A3/TX4/SDA1") (pinfunction "17-A3/TX4/SDA1_17-A3/TX4/SDA1") (pintype "bidirectional"))
    )
    (net (code "104") (name "unconnected-(TEENSY4.1-Pad28-RX7)") (class "Default")
      (node (ref "TEENSY4.1") (pin "28-RX7") (pinfunction "28-RX7_28-RX7") (pintype "bidirectional"))
    )
    (net (code "105") (name "unconnected-(TEENSY4.1-Pad29-TX7)") (class "Default")
      (node (ref "TEENSY4.1") (pin "29-TX7") (pinfunction "29-TX7_29-TX7") (pintype "bidirectional"))
    )
    (net (code "106") (name "unconnected-(TEENSY4.1-Pad31-CTX3)") (class "Default")
      (node (ref "TEENSY4.1") (pin "31-CTX3") (pinfunction "31-CTX3_31-CTX3") (pintype "bidirectional"))
    )
    (net (code "107") (name "unconnected-(TEENSY4.1-Pad38-A14{slash}CS{slash}IN1)") (class "Default")
      (node (ref "TEENSY4.1") (pin "38-A14/CS/IN1") (pinfunction "38-A14/CS/IN1_38-A14/CS/IN1") (pintype "bidirectional"))
    )
    (net (code "108") (name "unconnected-(TEENSY4.1-Pad39-A15{slash}CS{slash}OUT1A)") (class "Default")
      (node (ref "TEENSY4.1") (pin "39-A15/CS/OUT1A") (pinfunction "39-A15/CS/OUT1A_39-A15/CS/OUT1A") (pintype "bidirectional"))
    )
    (net (code "109") (name "unconnected-(TEENSY4.1-Pad41-A17{slash}MISO1)") (class "Default")
      (node (ref "TEENSY4.1") (pin "41-A17/MISO1") (pinfunction "41-A17/MISO1_41-A17/MISO1") (pintype "bidirectional"))
    )
    (net (code "110") (name "unconnected-(TEENSY4.1-PadD+)") (class "Default")
      (node (ref "TEENSY4.1") (pin "D+") (pinfunction "D+_D+") (pintype "bidirectional"))
    )
    (net (code "111") (name "unconnected-(TEENSY4.1-PadD-)") (class "Default")
      (node (ref "TEENSY4.1") (pin "D-") (pinfunction "D-_D-") (pintype "bidirectional"))
    )
    (net (code "112") (name "unconnected-(TEENSY4.1-PadDM)") (class "Default")
      (node (ref "TEENSY4.1") (pin "DM") (pinfunction "DM_DM") (pintype "bidirectional"))
    )
    (net (code "113") (name "unconnected-(TEENSY4.1-PadDP)") (class "Default")
      (node (ref "TEENSY4.1") (pin "DP") (pinfunction "DP_DP") (pintype "bidirectional"))
    )
    (net (code "114") (name "unconnected-(TEENSY4.1-PadG)") (class "Default")
      (node (ref "TEENSY4.1") (pin "G") (pinfunction "G_G") (pintype "bidirectional"))
    )
    (net (code "115") (name "unconnected-(TEENSY4.1-PadLED)") (class "Default")
      (node (ref "TEENSY4.1") (pin "LED") (pinfunction "LED_LED") (pintype "bidirectional"))
    )
    (net (code "116") (name "unconnected-(TEENSY4.1-PadON{slash}OFF)") (class "Default")
      (node (ref "TEENSY4.1") (pin "ON/OFF") (pinfunction "ON/OFF_ON/OFF") (pintype "bidirectional"))
    )
    (net (code "117") (name "unconnected-(TEENSY4.1-PadPROGRAM)") (class "Default")
      (node (ref "TEENSY4.1") (pin "PROGRAM") (pinfunction "PROGRAM_PROGRAM") (pintype "bidirectional"))
    )
    (net (code "118") (name "unconnected-(TEENSY4.1-PadR+)") (class "Default")
      (node (ref "TEENSY4.1") (pin "R+") (pinfunction "R+_R+") (pintype "bidirectional"))
    )
    (net (code "119") (name "unconnected-(TEENSY4.1-PadR-)") (class "Default")
      (node (ref "TEENSY4.1") (pin "R-") (pinfunction "R-_R-") (pintype "bidirectional"))
    )
    (net (code "120") (name "unconnected-(TEENSY4.1-PadT+)") (class "Default")
      (node (ref "TEENSY4.1") (pin "T+") (pinfunction "T+_T+") (pintype "bidirectional"))
    )
    (net (code "121") (name "unconnected-(TEENSY4.1-PadT-)") (class "Default")
      (node (ref "TEENSY4.1") (pin "T-") (pinfunction "T-_T-") (pintype "bidirectional"))
    )
    (net (code "122") (name "unconnected-(TEENSY4.1-PadVBAT)") (class "Default")
      (node (ref "TEENSY4.1") (pin "VBAT") (pinfunction "VBAT_VBAT") (pintype "bidirectional"))
    )
    (net (code "123") (name "unconnected-(TEENSY4.1-PadVUSB)") (class "Default")
      (node (ref "TEENSY4.1") (pin "VUSB") (pinfunction "VUSB_VUSB") (pintype "bidirectional"))
    )
  )
)
